# VEML7700_Breakout.net
KiCad netlist of a schematic drawn in EAGLE
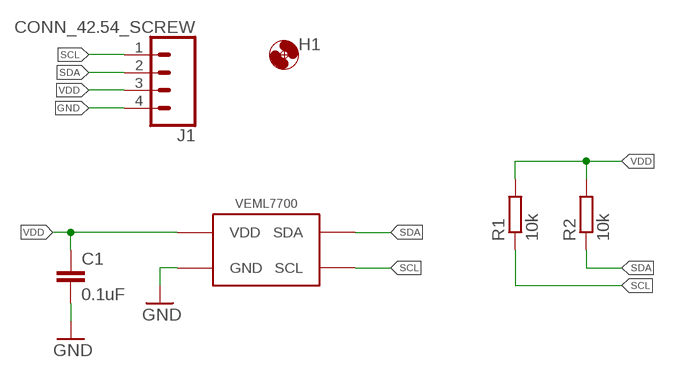
[diagram p0: schematic, sheet 1]

(export (version "E")
  (design (tool "Eeschema 10.0.6"))
  (components
    (comp (ref "C1")
      (value "0.1uF")
      (footprint "eagle-import:C0603")
      (fields (field (name "MF") "Murata") (field (name "MPN") "GCM188R71E104KA57D"))
      (libsource (lib "eagle-import") (part "C-EUC06030.1UF"))
    )
    (comp (ref "H1")
      (value "MOUNTING_HOLE2_NP")
      (footprint "eagle-import:2_56")
      (fields (field (name "MPN") "DNP"))
      (libsource (lib "eagle-import") (part "MOUNTING_HOLE2_NP"))
    )
    (comp (ref "J1")
      (value "CONN_42.54_SCREW")
      (footprint "eagle-import:1X04_SCREW")
      (fields (field (name "MF") "On Shore") (field (name "MPN") "OSTVN04A150"))
      (libsource (lib "eagle-import") (part "CONN_42.54_SCREW"))
    )
    (comp (ref "R1")
      (value "10k")
      (footprint "eagle-import:R0603")
      (fields (field (name "MF") "Yageo") (field (name "MPN") "RC0603FR-0710KL"))
      (libsource (lib "eagle-import") (part "R-EU_R060310K"))
    )
    (comp (ref "R2")
      (value "10k")
      (footprint "eagle-import:R0603")
      (fields (field (name "MF") "Yageo") (field (name "MPN") "RC0603FR-0710KL"))
      (libsource (lib "eagle-import") (part "R-EU_R060310K"))
    )
    (comp (ref "U1")
      (value "VEML7700")
      (footprint "eagle-import:VEML7700")
      (fields
        (field (name "DISP") "VEML7700")
        (field (name "MF") "Vishay")
        (field (name "MPN") "VEML7700-TR")
      )
      (libsource (lib "eagle-import") (part "VEML7700"))
    )
  )
  (nets
    (net (code "1") (name "GND") (class "Default")
      (node (ref "C1") (pin "2") (pinfunction "2_2") (pintype "passive"))
      (node (ref "J1") (pin "4") (pinfunction "4_4") (pintype "passive"))
      (node (ref "U1") (pin "3") (pinfunction "GND_3") (pintype "power_in"))
    )
    (net (code "2") (name "SCL") (class "Default")
      (node (ref "J1") (pin "1") (pinfunction "1_1") (pintype "passive"))
      (node (ref "R1") (pin "1") (pinfunction "1_1") (pintype "passive"))
      (node (ref "U1") (pin "1") (pinfunction "SCL_1") (pintype "input"))
    )
    (net (code "3") (name "SDA") (class "Default")
      (node (ref "J1") (pin "2") (pinfunction "2_2") (pintype "passive"))
      (node (ref "R2") (pin "1") (pinfunction "1_1") (pintype "passive"))
      (node (ref "U1") (pin "4") (pinfunction "SDA_4") (pintype "bidirectional"))
    )
    (net (code "4") (name "VDD") (class "Default")
      (node (ref "C1") (pin "1") (pinfunction "1_1") (pintype "passive"))
      (node (ref "J1") (pin "3") (pinfunction "3_3") (pintype "passive"))
      (node (ref "R1") (pin "2") (pinfunction "2_2") (pintype "passive"))
      (node (ref "R2") (pin "2") (pinfunction "2_2") (pintype "passive"))
      (node (ref "U1") (pin "2") (pinfunction "VDD_2") (pintype "power_in"))
    )
  )
)
